# 48V_Converter_Sub.net
KiCad netlist of a schematic drawn in Altium Designer
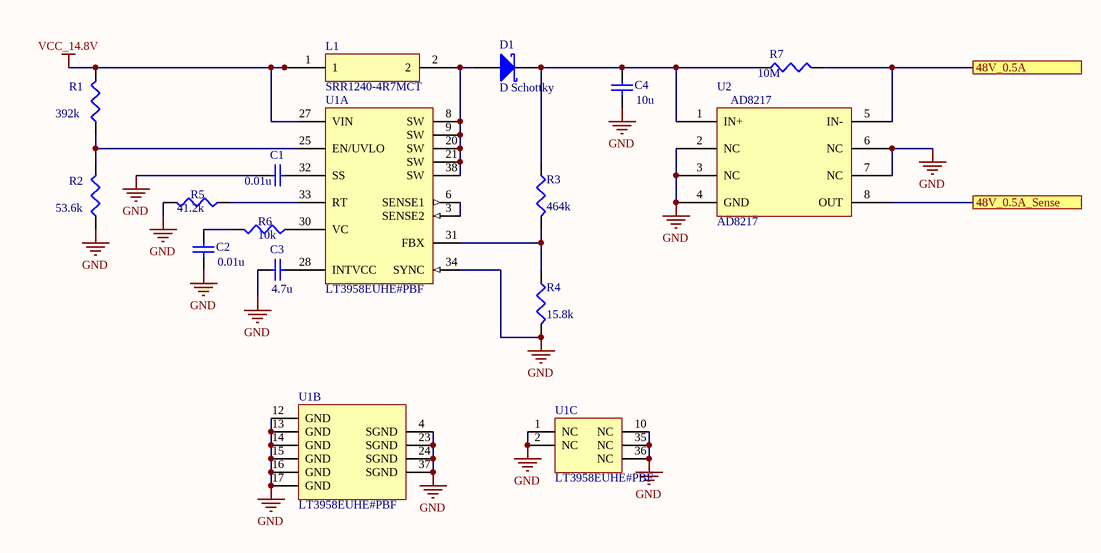
[diagram p0: 48V_Converter_Sub.SchDoc]

(export (version "E")
  (design (tool "Eeschema 10.0.6"))
  (components
    (comp (ref "C1")
      (value "0.01u")
      (footprint "C1206")
      (description "Capacitor (Semiconductor SIM Model)")
      (fields (field (name "Comment") "Cap Semi") (field (name "PUBLISHER") "Altium Limited"))
      (libsource (lib "Miscellaneous Devices") (part "Cap Semi"))
    )
    (comp (ref "C2")
      (value "0.01u")
      (footprint "C1206")
      (description "Capacitor (Semiconductor SIM Model)")
      (fields (field (name "Comment") "Cap Semi") (field (name "PUBLISHER") "Altium Limited"))
      (libsource (lib "Miscellaneous Devices") (part "Cap Semi"))
    )
    (comp (ref "C3")
      (value "4.7u")
      (footprint "C1206")
      (description "Capacitor (Semiconductor SIM Model)")
      (fields (field (name "Comment") "Cap Semi") (field (name "PUBLISHER") "Altium Limited"))
      (libsource (lib "Miscellaneous Devices") (part "Cap Semi"))
    )
    (comp (ref "C4")
      (value "10u")
      (footprint "C1206")
      (description "Capacitor (Semiconductor SIM Model)")
      (fields (field (name "Comment") "Cap Semi") (field (name "PUBLISHER") "Altium Limited"))
      (libsource (lib "Miscellaneous Devices") (part "Cap Semi"))
    )
    (comp (ref "D1")
      (value "D Schottky")
      (footprint "SMB")
      (description "Schottky Diode")
      (fields (field (name "PUBLISHER") "Altium Limited"))
      (libsource (lib "Miscellaneous Devices") (part "D Schottky"))
    )
    (comp (ref "L1")
      (value "SRR1240-4R7MCT")
      (footprint "SRR1240-4R7M")
      (libsource (lib "Power_Board_Parts_Library") (part "SRR1240-4R7MCT"))
    )
    (comp (ref "R1")
      (value "392k")
      (footprint "J1-0603")
      (description "Resistor")
      (fields (field (name "Comment") "Res3") (field (name "PUBLISHER") "Altium Limited"))
      (libsource (lib "Miscellaneous Devices") (part "Res3"))
    )
    (comp (ref "R2")
      (value "53.6k")
      (footprint "J1-0603")
      (description "Resistor")
      (fields (field (name "Comment") "Res3") (field (name "PUBLISHER") "Altium Limited"))
      (libsource (lib "Miscellaneous Devices") (part "Res3"))
    )
    (comp (ref "R3")
      (value "464k")
      (footprint "J1-0603")
      (description "Resistor")
      (fields (field (name "Comment") "Res3") (field (name "PUBLISHER") "Altium Limited"))
      (libsource (lib "Miscellaneous Devices") (part "Res3"))
    )
    (comp (ref "R4")
      (value "15.8k")
      (footprint "J1-0603")
      (description "Resistor")
      (fields (field (name "Comment") "Res3") (field (name "PUBLISHER") "Altium Limited"))
      (libsource (lib "Miscellaneous Devices") (part "Res3"))
    )
    (comp (ref "R5")
      (value "41.2k")
      (footprint "J1-0603")
      (description "Resistor")
      (fields (field (name "Comment") "Res3") (field (name "PUBLISHER") "Altium Limited"))
      (libsource (lib "Miscellaneous Devices") (part "Res3"))
    )
    (comp (ref "R6")
      (value "10k")
      (footprint "J1-0603")
      (description "Resistor")
      (fields (field (name "Comment") "Res3") (field (name "PUBLISHER") "Altium Limited"))
      (libsource (lib "Miscellaneous Devices") (part "Res3"))
    )
    (comp (ref "R7")
      (value "10M")
      (footprint "J1-0603")
      (description "Resistor")
      (fields (field (name "Comment") "Res3") (field (name "PUBLISHER") "Altium Limited"))
      (libsource (lib "Miscellaneous Devices") (part "Res3"))
    )
    (comp (ref "U1")
      (value "LT3958EUHE#PBF")
      (footprint "LT-UHE-36-V-UHE28MA_V")
      (fields (field (name "MANUFACTURER") "Linear Technology"))
      (libsource (lib "Linear Technology Power Management Switching Regulator LT1074-LT8705") (part "LT3958EUHE#PBF"))
    )
    (comp (ref "U2")
      (value "AD8217")
      (footprint "AD8217")
      (description "Current Sense")
      (libsource (lib "AD8217_Currentsense") (part "AD8217"))
    )
  )
  (nets
    (net (code "1") (name "/48V_0.5A") (class "Default")
      (node (ref "R7") (pin "2") (pinfunction "2_2") (pintype "passive"))
      (node (ref "U2") (pin "5") (pinfunction "IN-_5") (pintype "passive"))
    )
    (net (code "2") (name "/48V_0.5A_Sense") (class "Default")
      (node (ref "U2") (pin "8") (pinfunction "OUT_8") (pintype "passive"))
    )
    (net (code "3") (name "GND") (class "Default")
      (node (ref "C1") (pin "2") (pinfunction "2_2") (pintype "passive"))
      (node (ref "C2") (pin "2") (pinfunction "2_2") (pintype "passive"))
      (node (ref "C3") (pin "2") (pinfunction "2_2") (pintype "passive"))
      (node (ref "C4") (pin "2") (pinfunction "2_2") (pintype "passive"))
      (node (ref "R2") (pin "1") (pinfunction "1_1") (pintype "passive"))
      (node (ref "R4") (pin "2") (pinfunction "2_2") (pintype "passive"))
      (node (ref "R5") (pin "2") (pinfunction "2_2") (pintype "passive"))
      (node (ref "U1") (pin "1") (pinfunction "NC_1") (pintype "passive"))
      (node (ref "U1") (pin "10") (pinfunction "NC_10") (pintype "passive"))
      (node (ref "U1") (pin "12") (pinfunction "GND_12") (pintype "power_in"))
      (node (ref "U1") (pin "13") (pinfunction "GND_13") (pintype "power_in"))
      (node (ref "U1") (pin "14") (pinfunction "GND_14") (pintype "power_in"))
      (node (ref "U1") (pin "15") (pinfunction "GND_15") (pintype "power_in"))
      (node (ref "U1") (pin "16") (pinfunction "GND_16") (pintype "power_in"))
      (node (ref "U1") (pin "17") (pinfunction "GND_17") (pintype "power_in"))
      (node (ref "U1") (pin "2") (pinfunction "NC_2") (pintype "passive"))
      (node (ref "U1") (pin "23") (pinfunction "SGND_23") (pintype "power_in"))
      (node (ref "U1") (pin "24") (pinfunction "SGND_24") (pintype "power_in"))
      (node (ref "U1") (pin "34") (pinfunction "SYNC_34") (pintype "input"))
      (node (ref "U1") (pin "35") (pinfunction "NC_35") (pintype "passive"))
      (node (ref "U1") (pin "36") (pinfunction "NC_36") (pintype "passive"))
      (node (ref "U1") (pin "37") (pinfunction "SGND_37") (pintype "power_in"))
      (node (ref "U1") (pin "4") (pinfunction "SGND_4") (pintype "power_in"))
      (node (ref "U2") (pin "2") (pinfunction "NC_2") (pintype "passive"))
      (node (ref "U2") (pin "3") (pinfunction "NC_3") (pintype "passive"))
      (node (ref "U2") (pin "4") (pinfunction "GND_4") (pintype "passive"))
      (node (ref "U2") (pin "6") (pinfunction "NC_6") (pintype "passive"))
      (node (ref "U2") (pin "7") (pinfunction "NC_7") (pintype "passive"))
    )
    (net (code "4") (name "Net-(C2-Pad1)") (class "Default")
      (node (ref "C2") (pin "1") (pinfunction "1_1") (pintype "passive"))
      (node (ref "R6") (pin "2") (pinfunction "2_2") (pintype "passive"))
    )
    (net (code "5") (name "Net-(D1-A)") (class "Default")
      (node (ref "D1") (pin "1") (pinfunction "A_1") (pintype "passive"))
      (node (ref "L1") (pin "2") (pinfunction "2_2") (pintype "passive"))
      (node (ref "U1") (pin "20") (pinfunction "SW_20") (pintype "power_in"))
      (node (ref "U1") (pin "21") (pinfunction "SW_21") (pintype "power_in"))
      (node (ref "U1") (pin "38") (pinfunction "SW_38") (pintype "power_in"))
      (node (ref "U1") (pin "8") (pinfunction "SW_8") (pintype "power_in"))
      (node (ref "U1") (pin "9") (pinfunction "SW_9") (pintype "power_in"))
    )
    (net (code "6") (name "Net-(D1-K)") (class "Default")
      (node (ref "C4") (pin "1") (pinfunction "1_1") (pintype "passive"))
      (node (ref "D1") (pin "2") (pinfunction "K_2") (pintype "passive"))
      (node (ref "R3") (pin "1") (pinfunction "1_1") (pintype "passive"))
      (node (ref "R7") (pin "1") (pinfunction "1_1") (pintype "passive"))
      (node (ref "U2") (pin "1") (pinfunction "IN+_1") (pintype "passive"))
    )
    (net (code "7") (name "Net-(U1A-EN{slash}UVLO)") (class "Default")
      (node (ref "R1") (pin "1") (pinfunction "1_1") (pintype "passive"))
      (node (ref "R2") (pin "2") (pinfunction "2_2") (pintype "passive"))
      (node (ref "U1") (pin "25") (pinfunction "EN/UVLO_25") (pintype "input"))
    )
    (net (code "8") (name "Net-(U1A-FBX)") (class "Default")
      (node (ref "R3") (pin "2") (pinfunction "2_2") (pintype "passive"))
      (node (ref "R4") (pin "1") (pinfunction "1_1") (pintype "passive"))
      (node (ref "U1") (pin "31") (pinfunction "FBX_31") (pintype "input"))
    )
    (net (code "9") (name "Net-(U1A-INTVCC)") (class "Default")
      (node (ref "C3") (pin "1") (pinfunction "1_1") (pintype "passive"))
      (node (ref "U1") (pin "28") (pinfunction "INTVCC_28") (pintype "power_in"))
    )
    (net (code "10") (name "Net-(U1A-RT)") (class "Default")
      (node (ref "R5") (pin "1") (pinfunction "1_1") (pintype "passive"))
      (node (ref "U1") (pin "33") (pinfunction "RT_33") (pintype "passive"))
    )
    (net (code "11") (name "Net-(U1A-SENSE1)") (class "Default")
      (node (ref "U1") (pin "3") (pinfunction "SENSE2_3") (pintype "input"))
      (node (ref "U1") (pin "6") (pinfunction "SENSE1_6") (pintype "output"))
    )
    (net (code "12") (name "Net-(U1A-SS)") (class "Default")
      (node (ref "C1") (pin "1") (pinfunction "1_1") (pintype "passive"))
      (node (ref "U1") (pin "32") (pinfunction "SS_32") (pintype "input"))
    )
    (net (code "13") (name "Net-(U1A-VC)") (class "Default")
      (node (ref "R6") (pin "1") (pinfunction "1_1") (pintype "passive"))
      (node (ref "U1") (pin "30") (pinfunction "VC_30") (pintype "passive"))
    )
    (net (code "14") (name "VCC_14.8V") (class "Default")
      (node (ref "L1") (pin "1") (pinfunction "1_1") (pintype "passive"))
      (node (ref "R1") (pin "2") (pinfunction "2_2") (pintype "passive"))
      (node (ref "U1") (pin "27") (pinfunction "VIN_27") (pintype "power_in"))
    )
  )
)
